# USB.net
KiCad netlist of a schematic drawn in Altium Designer
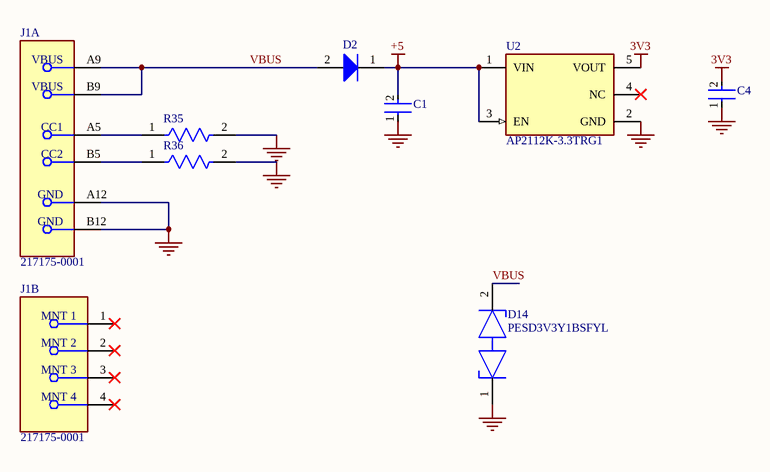
[diagram p0: USB.SchDoc]

(export (version "E")
  (design (tool "Eeschema 10.0.6"))
  (components
    (comp (ref "C1")
      (value "C1608X5R1H105K080AB")
      (footprint "FP-C1608-080-0_1-IPC_B")
      (description "Multilayer Ceramic Capacitors 1μF ±10% 50V X5R SMD 0603")
      (fields (field (name "VOLTAGE") "50V") (field (name "TOLERANCE") "10%"))
      (libsource (lib "Altium Content Vault") (part "236180d848d6139a670b325ea6854c9"))
    )
    (comp (ref "C4")
      (value "C1608X5R1H105K080AB")
      (footprint "FP-C1608-080-0_1-IPC_B")
      (description "Multilayer Ceramic Capacitors 1μF ±10% 50V X5R SMD 0603")
      (fields (field (name "VOLTAGE") "50V") (field (name "TOLERANCE") "10%"))
      (libsource (lib "Altium Content Vault") (part "236180d848d6139a670b325ea6854c9"))
    )
    (comp (ref "D2")
      (value "NSR0320MW2T1G")
      (footprint "ONSC-SOD-323-2-477-02_V")
      (description "Schottky Barrier Diode, 2-Pin SOD-323, Pb-Free, Tape and Reel")
      (fields (field (name "MANUFACTURER") "On Semiconductor"))
      (libsource (lib "Altium Content Vault") (part "ONSC-D-K1A2-2"))
    )
    (comp (ref "D14")
      (value "PESD3V3Y1BSFYL")
      (footprint "FP-SOD962-2-CA-MFG")
      (description "PESD3V3Y1BSFYL PESD4V0Y1BSF - Extremely low capacitance bidirectional ESD protection diode")
      (libsource (lib "Altium Content Vault") (part "3f15ade4c48aeaca3578241bea7d4a4"))
    )
    (comp (ref "J1")
      (value "217175-0001")
      (footprint "FP-217175-0001-MFG")
      (description "CONN RCP USB2.0 C 6+18P SMD RA")
      (libsource (lib "Altium Content Vault") (part "6a66c69350f09309f94811689c98437"))
    )
    (comp (ref "R35")
      (value "RN73R1ETTP5101F25")
      (footprint "FP-RN73R1E-IPC_C")
      (description "5.1kΩ ±1% 0.063W, 1/16W Chip Resistor 0402 (1005 Metric) Moisture Resistant Thin Film")
      (libsource (lib "Altium Content Vault") (part "1029c3af85768c4190bb7ad29bc67b5"))
    )
    (comp (ref "R36")
      (value "RN73R1ETTP5101F25")
      (footprint "FP-RN73R1E-IPC_C")
      (description "5.1kΩ ±1% 0.063W, 1/16W Chip Resistor 0402 (1005 Metric) Moisture Resistant Thin Film")
      (libsource (lib "Altium Content Vault") (part "1029c3af85768c4190bb7ad29bc67b5"))
    )
    (comp (ref "U2")
      (value "AP2112K-3.3TRG1")
      (footprint "FP-SOT25-IPC_A")
      (description "IC REG LINEAR 3.3V 600MA SOT25")
      (libsource (lib "Altium Content Vault") (part "c8ab751aee5229183125ab046a11caa"))
    )
  )
  (nets
    (net (code "1") (name "+5") (class "Default")
      (node (ref "C1") (pin "2") (pinfunction "2_2") (pintype "passive"))
      (node (ref "D2") (pin "1") (pinfunction "K_1") (pintype "passive"))
      (node (ref "U2") (pin "1") (pinfunction "VIN_1") (pintype "power_in"))
      (node (ref "U2") (pin "3") (pinfunction "EN_3") (pintype "input"))
    )
    (net (code "2") (name "/VBUS") (class "Default")
      (node (ref "D14") (pin "2") (pinfunction "2_2") (pintype "passive"))
      (node (ref "D2") (pin "2") (pinfunction "A_2") (pintype "passive"))
      (node (ref "J1") (pin "A9") (pinfunction "VBUS_A9") (pintype "power_in"))
      (node (ref "J1") (pin "B9") (pinfunction "VBUS_B9") (pintype "power_in"))
    )
    (net (code "3") (name "3V3") (class "Default")
      (node (ref "C4") (pin "2") (pinfunction "2_2") (pintype "passive"))
      (node (ref "U2") (pin "5") (pinfunction "VOUT_5") (pintype "power_in"))
    )
    (net (code "4") (name "GND") (class "Default")
      (node (ref "C1") (pin "1") (pinfunction "1_1") (pintype "passive"))
      (node (ref "C4") (pin "1") (pinfunction "1_1") (pintype "passive"))
      (node (ref "D14") (pin "1") (pinfunction "1_1") (pintype "passive"))
      (node (ref "J1") (pin "A12") (pinfunction "GND_A12") (pintype "power_in"))
      (node (ref "J1") (pin "B12") (pinfunction "GND_B12") (pintype "power_in"))
      (node (ref "R35") (pin "2") (pinfunction "2_2") (pintype "passive"))
      (node (ref "R36") (pin "2") (pinfunction "2_2") (pintype "passive"))
      (node (ref "U2") (pin "2") (pinfunction "GND_2") (pintype "power_in"))
    )
    (net (code "5") (name "Net-(J1A-CC1)") (class "Default")
      (node (ref "J1") (pin "A5") (pinfunction "CC1_A5") (pintype "passive"))
      (node (ref "R35") (pin "1") (pinfunction "1_1") (pintype "passive"))
    )
    (net (code "6") (name "Net-(J1A-CC2)") (class "Default")
      (node (ref "J1") (pin "B5") (pinfunction "CC2_B5") (pintype "passive"))
      (node (ref "R36") (pin "1") (pinfunction "1_1") (pintype "passive"))
    )
    (net (code "7") (name "unconnected-(J1B-MNT_1-Pad1)") (class "Default")
      (node (ref "J1") (pin "1") (pinfunction "MNT_1_1") (pintype "passive+no_connect"))
    )
    (net (code "8") (name "unconnected-(J1B-MNT_2-Pad2)") (class "Default")
      (node (ref "J1") (pin "2") (pinfunction "MNT_2_2") (pintype "passive+no_connect"))
    )
    (net (code "9") (name "unconnected-(J1B-MNT_3-Pad3)") (class "Default")
      (node (ref "J1") (pin "3") (pinfunction "MNT_3_3") (pintype "passive+no_connect"))
    )
    (net (code "10") (name "unconnected-(J1B-MNT_4-Pad4)") (class "Default")
      (node (ref "J1") (pin "4") (pinfunction "MNT_4_4") (pintype "passive+no_connect"))
    )
    (net (code "11") (name "unconnected-(U2-NC-Pad4)") (class "Default")
      (node (ref "U2") (pin "4") (pinfunction "NC_4") (pintype "passive+no_connect"))
    )
  )
)
